# BrauV2_RS485.net
KiCad netlist of a schematic drawn in Altium Designer
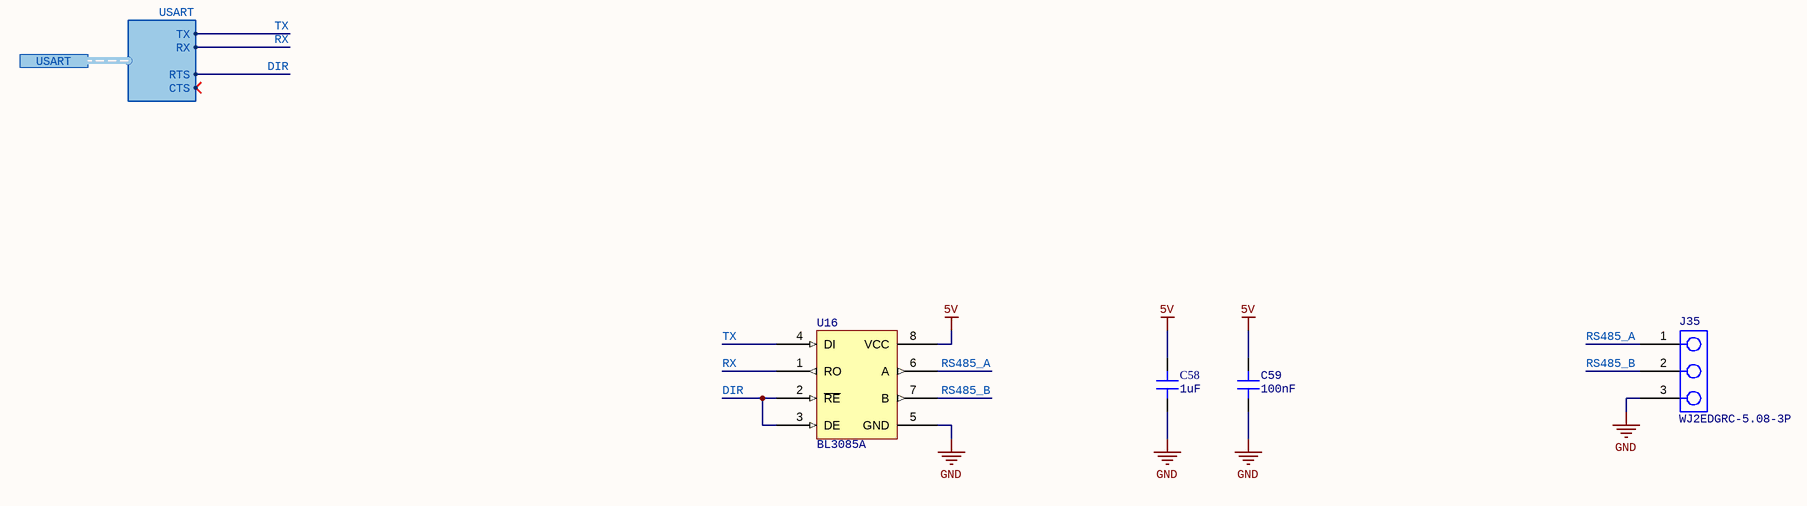
[diagram p0: BrauV2_RS485.SchDoc]

(export (version "E")
  (design (tool "Eeschema 10.0.6"))
  (components
    (comp (ref "C58")
      (value "CC0603KRX5R9BB105")
      (footprint "SMD_CAP_0603(0201)_N")
      (description "1uF ±10% 50V X5R 0603 Multilayer Ceramic Capacitors MLCC - SMD/SMT RoHS")
      (fields (field (name "TOLERANCE") "10%") (field (name "CAPACITANCE") "1uF"))
      (libsource (lib "BrauV2_Capacitor") (part "1uF 0603 50V 10%"))
    )
    (comp (ref "C59")
      (value "CC0402KRX5R6BB104")
      (footprint "SMD_CAP_0402(1005)_N")
      (description "100nF ±10% 10V X5R 0402 Multilayer Ceramic Capacitors MLCC - SMD/SMT RoHS")
      (fields (field (name "TOLERANCE") "10%") (field (name "CAPACITANCE") "100nF"))
      (libsource (lib "BrauV2_Capacitor") (part "100nF 0402 10V 10%"))
    )
    (comp (ref "J35")
      (value "WJ2EDGRC-5.08-3P")
      (footprint "796638-3")
      (description "Covered（4Sided） 3 1 0.200\"（5.08mm） 3 P=5.08mm Pluggable System Terminal Block RoHS")
      (libsource (lib "BrauV2_Connector") (part "WJ2EDGRC-5.08-3P"))
    )
    (comp (ref "U16")
      (value "BL3085A")
      (footprint "SOIC-8-3.9mm")
      (description "SOIC-8_150mil RS-485/RS-422 ICs ROHS (MAX485 clone)")
      (libsource (lib "BrauV2_IC") (part "BL3085A"))
    )
  )
  (nets
    (net (code "2") (name "/DIR") (class "Default")
      (node (ref "U16") (pin "2") (pinfunction "~{RE}_2") (pintype "input"))
      (node (ref "U16") (pin "3") (pinfunction "DE_3") (pintype "input"))
    )
    (net (code "3") (name "/RS485_A") (class "Default")
      (node (ref "J35") (pin "1") (pinfunction "1_1") (pintype "passive"))
      (node (ref "U16") (pin "6") (pinfunction "A_6") (pintype "output"))
    )
    (net (code "4") (name "/RS485_B") (class "Default")
      (node (ref "J35") (pin "2") (pinfunction "2_2") (pintype "passive"))
      (node (ref "U16") (pin "7") (pinfunction "B_7") (pintype "output"))
    )
    (net (code "5") (name "/RX") (class "Default")
      (node (ref "U16") (pin "1") (pinfunction "RO_1") (pintype "output"))
    )
    (net (code "6") (name "/TX") (class "Default")
      (node (ref "U16") (pin "4") (pinfunction "DI_4") (pintype "input"))
    )
    (net (code "8") (name "5V") (class "Default")
      (node (ref "C58") (pin "2") (pinfunction "2_2") (pintype "passive"))
      (node (ref "C59") (pin "2") (pinfunction "2_2") (pintype "passive"))
      (node (ref "U16") (pin "8") (pinfunction "VCC_8") (pintype "power_in"))
    )
    (net (code "9") (name "GND") (class "Default")
      (node (ref "C58") (pin "1") (pinfunction "1_1") (pintype "passive"))
      (node (ref "C59") (pin "1") (pinfunction "1_1") (pintype "passive"))
      (node (ref "J35") (pin "3") (pinfunction "3_3") (pintype "passive"))
      (node (ref "U16") (pin "5") (pinfunction "GND_5") (pintype "power_in"))
    )
  )
)
